# LLC_Demo_Board.net
KiCad netlist of a schematic drawn in EAGLE
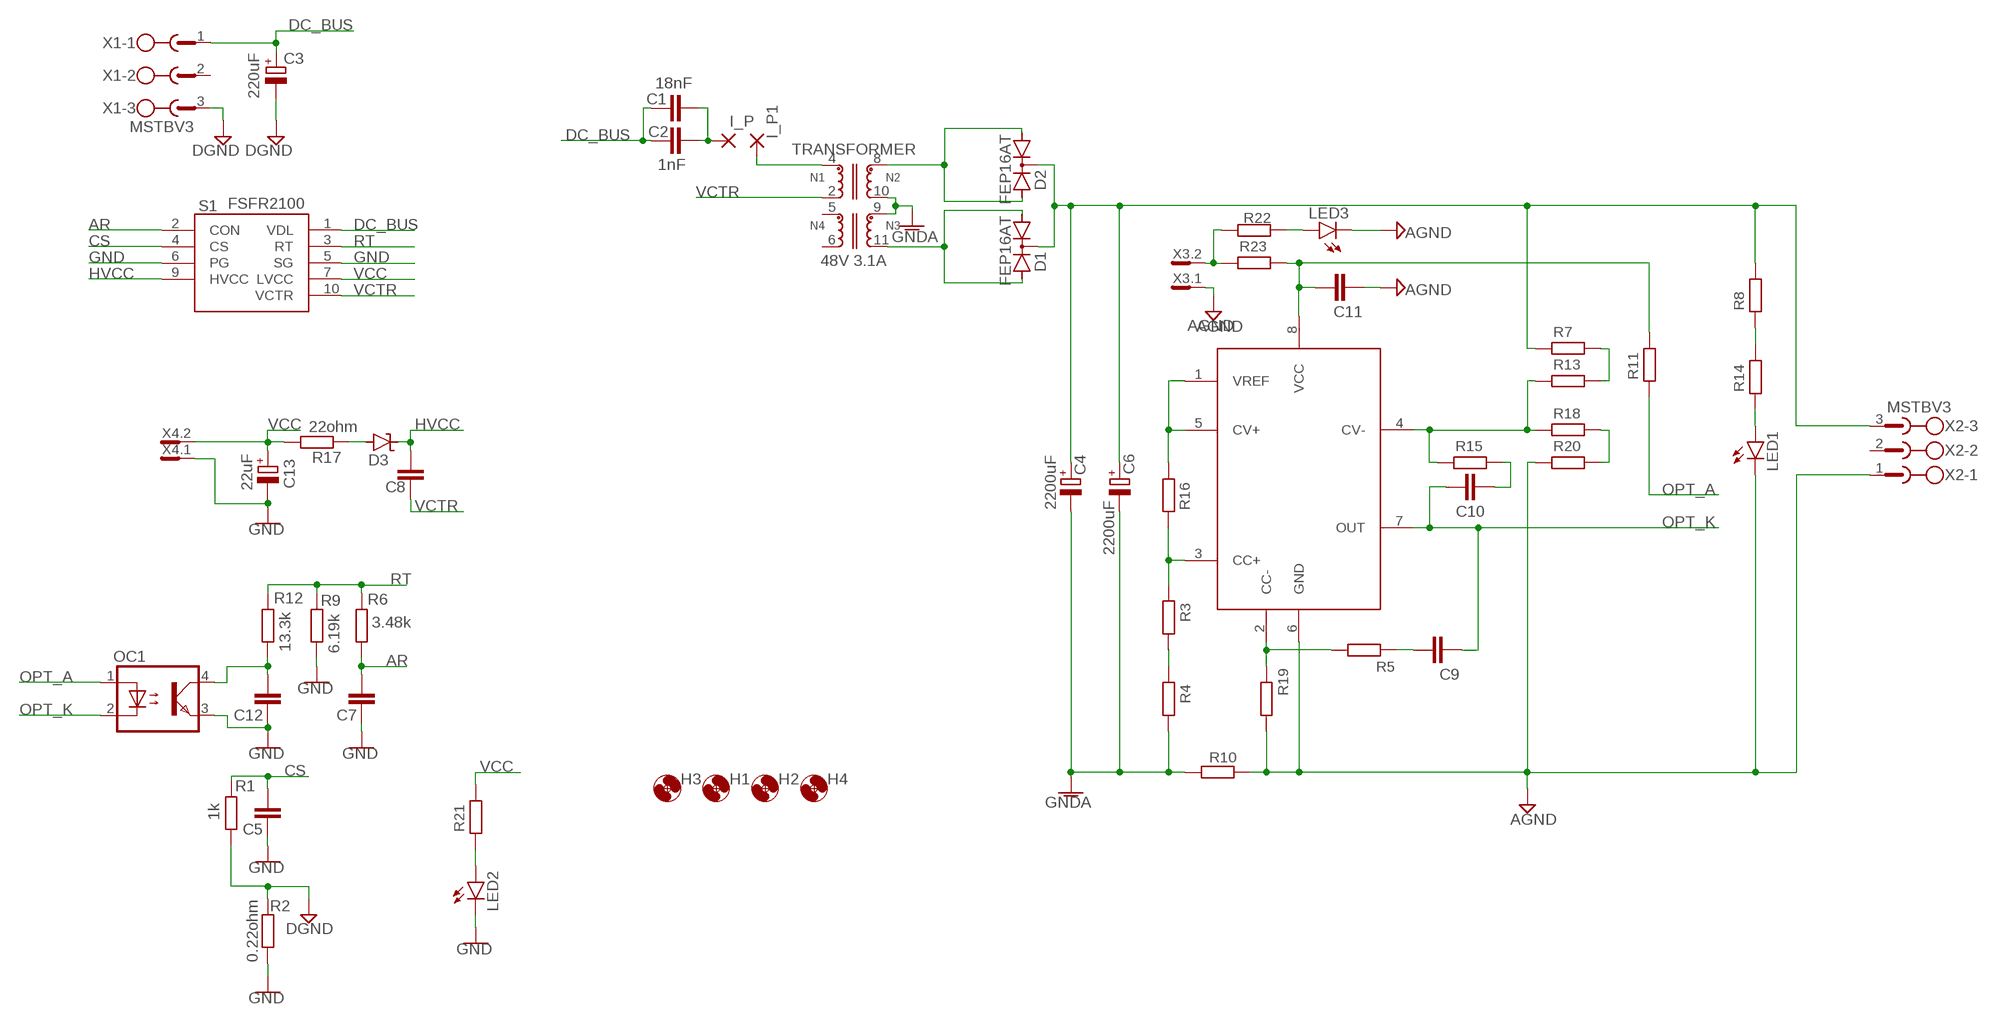
[diagram p0: schematic, sheet 1]

(export (version "E")
  (design (tool "Eeschema 10.0.6"))
  (components
    (comp (ref "C1")
      (value "18nF")
      (footprint "eagle-import:C075-063X106")
      (libsource (lib "eagle-import") (part "rcl_334_C-EU075-063X106"))
    )
    (comp (ref "C2")
      (value "1nF")
      (footprint "eagle-import:C150-072X183")
      (libsource (lib "eagle-import") (part "rcl_334_C-EU150-072X183"))
    )
    (comp (ref "C3")
      (value "220uF")
      (footprint "eagle-import:EB30D")
      (libsource (lib "eagle-import") (part "rcl_334_CPOL-EUE10-30"))
    )
    (comp (ref "C4")
      (value "2200uF")
      (footprint "eagle-import:E7,5-18")
      (libsource (lib "eagle-import") (part "CPOL-EUE7.5-18"))
    )
    (comp (ref "C5")
      (value "100pF")
      (footprint "eagle-import:C0805")
      (libsource (lib "eagle-import") (part "C-EUC0805"))
    )
    (comp (ref "C6")
      (value "2200uF")
      (footprint "eagle-import:E7,5-18")
      (libsource (lib "eagle-import") (part "CPOL-EUE7.5-18"))
    )
    (comp (ref "C7")
      (value "220nF")
      (footprint "eagle-import:C0805")
      (libsource (lib "eagle-import") (part "C-EUC0805"))
    )
    (comp (ref "C8")
      (value "150nF")
      (footprint "eagle-import:C1206")
      (libsource (lib "eagle-import") (part "C-EUC1206"))
    )
    (comp (ref "C9")
      (value "2.2nF")
      (footprint "eagle-import:C1206")
      (libsource (lib "eagle-import") (part "C-EUC1206"))
    )
    (comp (ref "C10")
      (value "2.2nF")
      (footprint "eagle-import:C1206")
      (libsource (lib "eagle-import") (part "C-EUC1206"))
    )
    (comp (ref "C11")
      (value "22uF")
      (footprint "eagle-import:C0805")
      (libsource (lib "eagle-import") (part "C-EUC0805"))
    )
    (comp (ref "C12")
      (value "12nF")
      (footprint "eagle-import:C0805")
      (libsource (lib "eagle-import") (part "C-EUC0805"))
    )
    (comp (ref "C13")
      (value "22uF")
      (footprint "eagle-import:153CLV-0605")
      (libsource (lib "eagle-import") (part "CPOL-EU153CLV-0605"))
    )
    (comp (ref "D1")
      (value "FEP16AT")
      (footprint "eagle-import:TO220ABS")
      (libsource (lib "eagle-import") (part "FEP16AT"))
    )
    (comp (ref "D2")
      (value "FEP16AT")
      (footprint "eagle-import:TO220ABS")
      (libsource (lib "eagle-import") (part "FEP16AT"))
    )
    (comp (ref "D3")
      (value "SUPPRESSOR-SMBJ")
      (footprint "eagle-import:SMBJ")
      (libsource (lib "eagle-import") (part "SUPPRESSOR-SMBJ"))
    )
    (comp (ref "H1")
      (value "MOUNT-HOLE4.1")
      (footprint "eagle-import:4,1")
      (libsource (lib "eagle-import") (part "MOUNT-HOLE4.1"))
    )
    (comp (ref "H2")
      (value "MOUNT-HOLE4.1")
      (footprint "eagle-import:4,1")
      (libsource (lib "eagle-import") (part "MOUNT-HOLE4.1"))
    )
    (comp (ref "H3")
      (value "MOUNT-HOLE4.1")
      (footprint "eagle-import:4,1")
      (libsource (lib "eagle-import") (part "MOUNT-HOLE4.1"))
    )
    (comp (ref "H4")
      (value "MOUNT-HOLE4.1")
      (footprint "eagle-import:4,1")
      (libsource (lib "eagle-import") (part "MOUNT-HOLE4.1"))
    )
    (comp (ref "IC1")
      (value "1039-2224 / TSM1011ID SO-8 Constant Voltage and Constant Current Controller")
      (footprint "eagle-import:SO-8")
      (libsource (lib "eagle-import") (part "TSM1011"))
    )
    (comp (ref "I_P")
      (value "3,81/1,4")
      (footprint "eagle-import:3,81_1,4")
      (libsource (lib "eagle-import") (part "3,81/1,4"))
    )
    (comp (ref "I_P1")
      (value "3,81/1,4")
      (footprint "eagle-import:3,81_1,4")
      (libsource (lib "eagle-import") (part "3,81/1,4"))
    )
    (comp (ref "LED1")
      (value "LED5MM")
      (footprint "eagle-import:LED5MM")
      (libsource (lib "eagle-import") (part "LED5MM"))
    )
    (comp (ref "LED2")
      (value "LED5MM")
      (footprint "eagle-import:LED5MM")
      (libsource (lib "eagle-import") (part "LED5MM"))
    )
    (comp (ref "LED3")
      (value "LED5MM")
      (footprint "eagle-import:LED5MM")
      (libsource (lib "eagle-import") (part "LED5MM"))
    )
    (comp (ref "OC1")
      (value "1039-2189 / Opto coupler CEL-Renesas PS2561DL2-1Y-V-E3-A (8mm creepage ) CTR:50-400")
      (footprint "eagle-import:PS2561DL2-1_OPTO")
      (libsource (lib "eagle-import") (part "PS2561DL2-1_OPTO"))
    )
    (comp (ref "R1")
      (value "1k")
      (footprint "eagle-import:R0805")
      (libsource (lib "eagle-import") (part "R-EU_R0805"))
    )
    (comp (ref "R2")
      (value "0.22ohm")
      (footprint "eagle-import:R2512")
      (libsource (lib "eagle-import") (part "R-EU_R2512"))
    )
    (comp (ref "R3")
      (value "500ohm")
      (footprint "eagle-import:R0805")
      (libsource (lib "eagle-import") (part "R-EU_R0805"))
    )
    (comp (ref "R4")
      (value "500ohm")
      (footprint "eagle-import:R0805")
      (libsource (lib "eagle-import") (part "R-EU_R0805"))
    )
    (comp (ref "R5")
      (value "22k")
      (footprint "eagle-import:R1206")
      (libsource (lib "eagle-import") (part "R-EU_R1206"))
    )
    (comp (ref "R6")
      (value "3.48k")
      (footprint "eagle-import:R0805")
      (libsource (lib "eagle-import") (part "R-EU_R0805"))
    )
    (comp (ref "R7")
      (value "180k")
      (footprint "eagle-import:R1206")
      (libsource (lib "eagle-import") (part "R-EU_R1206"))
    )
    (comp (ref "R8")
      (value "1029-3175 / RES 0805 22K %1")
      (footprint "eagle-import:R1206")
      (libsource (lib "eagle-import") (part "R-EU_R1206"))
    )
    (comp (ref "R9")
      (value "6.19k")
      (footprint "eagle-import:R0805")
      (libsource (lib "eagle-import") (part "R-EU_R0805"))
    )
    (comp (ref "R10")
      (value "50m")
      (footprint "eagle-import:R2512")
      (libsource (lib "eagle-import") (part "R-EU_R2512"))
    )
    (comp (ref "R11")
      (value "100ohm")
      (footprint "eagle-import:R1206")
      (libsource (lib "eagle-import") (part "R-EU_R1206"))
    )
    (comp (ref "R12")
      (value "13.3k")
      (footprint "eagle-import:R0805")
      (libsource (lib "eagle-import") (part "R-EU_R0805"))
    )
    (comp (ref "R13")
      (value "12k")
      (footprint "eagle-import:R1206")
      (libsource (lib "eagle-import") (part "R-EU_R1206"))
    )
    (comp (ref "R14")
      (value "1029-3175 / RES 0805 22K %1")
      (footprint "eagle-import:R1206")
      (libsource (lib "eagle-import") (part "R-EU_R1206"))
    )
    (comp (ref "R15")
      (value "22k")
      (footprint "eagle-import:R1206")
      (libsource (lib "eagle-import") (part "R-EU_R1206"))
    )
    (comp (ref "R16")
      (value "15k")
      (footprint "eagle-import:R0805")
      (libsource (lib "eagle-import") (part "R-EU_R0805"))
    )
    (comp (ref "R17")
      (value "22ohm")
      (footprint "eagle-import:R0805")
      (libsource (lib "eagle-import") (part "R-EU_R0805"))
    )
    (comp (ref "R18")
      (value "4.99k")
      (footprint "eagle-import:R1206")
      (libsource (lib "eagle-import") (part "R-EU_R1206"))
    )
    (comp (ref "R19")
      (value "1k")
      (footprint "eagle-import:R0805")
      (libsource (lib "eagle-import") (part "R-EU_R0805"))
    )
    (comp (ref "R20")
      (value "4.99k")
      (footprint "eagle-import:R1206")
      (libsource (lib "eagle-import") (part "R-EU_R1206"))
    )
    (comp (ref "R21")
      (value "1029-3175 / RES 0805 22K %1")
      (footprint "eagle-import:R1206")
      (libsource (lib "eagle-import") (part "R-EU_R1206"))
    )
    (comp (ref "R22")
      (value "1029-3175 / RES 0805 22K %1")
      (footprint "eagle-import:R1206")
      (libsource (lib "eagle-import") (part "R-EU_R1206"))
    )
    (comp (ref "R23")
      (value "1k")
      (footprint "eagle-import:R1206")
      (libsource (lib "eagle-import") (part "R-EU_R1206"))
    )
    (comp (ref "S1")
      (value "FSFR2100")
      (footprint "eagle-import:FSFR2100")
      (fields (field (name "MOUSER_PART_NUMBER") "512-FSFR2100") (field (name "RS_PART_NUMBER") "6710185P"))
      (libsource (lib "eagle-import") (part "FSFR2100"))
    )
    (comp (ref "TRANSFORMER")
      (value "48V 3.1A")
      (footprint "eagle-import:WE-LLCR_ETD34")
      (libsource (lib "eagle-import") (part "WE-LLCR_ETD34_760895451"))
    )
    (comp (ref "X1")
      (value "MSTBV3")
      (footprint "eagle-import:MSTBV3")
      (fields (field (name "MPN") "MSTBV 2,5/3-GF-5.08"))
      (libsource (lib "eagle-import") (part "MSTBV3"))
    )
    (comp (ref "X2")
      (value "MSTBV3")
      (footprint "eagle-import:MSTBV3")
      (fields (field (name "MPN") "MSTBV 2,5/3-GF-5.08"))
      (libsource (lib "eagle-import") (part "MSTBV3"))
    )
    (comp (ref "X3")
      (value "İKİLİ MOLEX")
      (footprint "eagle-import:MCV2")
      (libsource (lib "eagle-import") (part "MCV2"))
    )
    (comp (ref "X4")
      (value "İKİLİ MOLEX")
      (footprint "eagle-import:MCV2")
      (libsource (lib "eagle-import") (part "MCV2"))
    )
  )
  (nets
    (net (code "1") (name "/AR") (class "Default")
      (node (ref "C7") (pin "1") (pinfunction "1_1") (pintype "passive"))
      (node (ref "R6") (pin "2") (pinfunction "2_2") (pintype "passive"))
      (node (ref "S1") (pin "2") (pinfunction "CON_2") (pintype "bidirectional"))
    )
    (net (code "2") (name "/CS") (class "Default")
      (node (ref "C5") (pin "1") (pinfunction "1_1") (pintype "passive"))
      (node (ref "R1") (pin "2") (pinfunction "2_2") (pintype "passive"))
      (node (ref "S1") (pin "4") (pinfunction "CS_4") (pintype "bidirectional"))
    )
    (net (code "3") (name "/DC_BUS") (class "Default")
      (node (ref "C1") (pin "1") (pinfunction "1_1") (pintype "passive"))
      (node (ref "C2") (pin "1") (pinfunction "1_1") (pintype "passive"))
      (node (ref "C3") (pin "+") (pinfunction "+_+") (pintype "passive"))
      (node (ref "S1") (pin "1") (pinfunction "VDL_1") (pintype "bidirectional"))
      (node (ref "X1") (pin "1") (pinfunction "1_1") (pintype "passive"))
    )
    (net (code "4") (name "/HVCC") (class "Default")
      (node (ref "C8") (pin "1") (pinfunction "1_1") (pintype "passive"))
      (node (ref "D3") (pin "C") (pinfunction "C_C") (pintype "passive"))
      (node (ref "S1") (pin "9") (pinfunction "HVCC_9") (pintype "bidirectional"))
    )
    (net (code "5") (name "/OPT_A") (class "Default")
      (node (ref "OC1") (pin "1") (pinfunction "1_1") (pintype "passive"))
      (node (ref "R11") (pin "2") (pinfunction "2_2") (pintype "passive"))
    )
    (net (code "6") (name "/OPT_K") (class "Default")
      (node (ref "C10") (pin "1") (pinfunction "1_1") (pintype "passive"))
      (node (ref "C9") (pin "1") (pinfunction "1_1") (pintype "passive"))
      (node (ref "IC1") (pin "7") (pinfunction "OUT_7") (pintype "output"))
      (node (ref "OC1") (pin "2") (pinfunction "2_2") (pintype "passive"))
    )
    (net (code "7") (name "/RT") (class "Default")
      (node (ref "R12") (pin "1") (pinfunction "1_1") (pintype "passive"))
      (node (ref "R6") (pin "1") (pinfunction "1_1") (pintype "passive"))
      (node (ref "R9") (pin "1") (pinfunction "1_1") (pintype "passive"))
      (node (ref "S1") (pin "3") (pinfunction "RT_3") (pintype "bidirectional"))
    )
    (net (code "8") (name "/VCC") (class "Default")
      (node (ref "C13") (pin "+") (pinfunction "+_+") (pintype "passive"))
      (node (ref "R17") (pin "2") (pinfunction "2_2") (pintype "passive"))
      (node (ref "R21") (pin "1") (pinfunction "1_1") (pintype "passive"))
      (node (ref "S1") (pin "7") (pinfunction "LVCC_7") (pintype "bidirectional"))
      (node (ref "X4") (pin "2") (pinfunction "SK_2") (pintype "passive"))
    )
    (net (code "9") (name "/VCTR") (class "Default")
      (node (ref "C8") (pin "2") (pinfunction "2_2") (pintype "passive"))
      (node (ref "S1") (pin "10") (pinfunction "VCTR_10") (pintype "bidirectional"))
      (node (ref "TRANSFORMER") (pin "2") (pinfunction "2_2") (pintype "passive"))
    )
    (net (code "10") (name "AGND") (class "Default")
      (node (ref "C11") (pin "1") (pinfunction "1_1") (pintype "passive"))
      (node (ref "IC1") (pin "6") (pinfunction "GND_6") (pintype "power_in"))
      (node (ref "LED1") (pin "K") (pinfunction "C_K") (pintype "passive"))
      (node (ref "LED3") (pin "K") (pinfunction "C_K") (pintype "passive"))
      (node (ref "R10") (pin "2") (pinfunction "2_2") (pintype "passive"))
      (node (ref "R19") (pin "1") (pinfunction "1_1") (pintype "passive"))
      (node (ref "R20") (pin "2") (pinfunction "2_2") (pintype "passive"))
      (node (ref "X2") (pin "1") (pinfunction "1_1") (pintype "passive"))
      (node (ref "X3") (pin "1") (pinfunction "SK_1") (pintype "passive"))
    )
    (net (code "11") (name "DGND") (class "Default")
      (node (ref "C3") (pin "-") (pinfunction "-_-") (pintype "passive"))
      (node (ref "R1") (pin "1") (pinfunction "1_1") (pintype "passive"))
      (node (ref "R2") (pin "2") (pinfunction "2_2") (pintype "passive"))
      (node (ref "X1") (pin "3") (pinfunction "1_3") (pintype "passive"))
    )
    (net (code "12") (name "GND") (class "Default")
      (node (ref "C12") (pin "2") (pinfunction "2_2") (pintype "passive"))
      (node (ref "C13") (pin "-") (pinfunction "-_-") (pintype "passive"))
      (node (ref "C5") (pin "2") (pinfunction "2_2") (pintype "passive"))
      (node (ref "C7") (pin "2") (pinfunction "2_2") (pintype "passive"))
      (node (ref "LED2") (pin "K") (pinfunction "C_K") (pintype "passive"))
      (node (ref "OC1") (pin "3") (pinfunction "3_3") (pintype "passive"))
      (node (ref "R2") (pin "1") (pinfunction "1_1") (pintype "passive"))
      (node (ref "R9") (pin "2") (pinfunction "2_2") (pintype "passive"))
      (node (ref "S1") (pin "5") (pinfunction "SG_5") (pintype "bidirectional"))
      (node (ref "S1") (pin "6") (pinfunction "PG_6") (pintype "bidirectional"))
      (node (ref "X4") (pin "1") (pinfunction "SK_1") (pintype "passive"))
    )
    (net (code "13") (name "GNDA") (class "Default")
      (node (ref "C4") (pin "-") (pinfunction "-_-") (pintype "passive"))
      (node (ref "C6") (pin "-") (pinfunction "-_-") (pintype "passive"))
      (node (ref "R10") (pin "1") (pinfunction "1_1") (pintype "passive"))
      (node (ref "R4") (pin "1") (pinfunction "1_1") (pintype "passive"))
      (node (ref "TRANSFORMER") (pin "10") (pinfunction "7_10") (pintype "passive"))
      (node (ref "TRANSFORMER") (pin "9") (pinfunction "6_9") (pintype "passive"))
    )
    (net (code "14") (name "Net-(C9-Pad2)") (class "Default")
      (node (ref "C9") (pin "2") (pinfunction "2_2") (pintype "passive"))
      (node (ref "R5") (pin "2") (pinfunction "2_2") (pintype "passive"))
    )
    (net (code "15") (name "Net-(C10-Pad2)") (class "Default")
      (node (ref "C10") (pin "2") (pinfunction "2_2") (pintype "passive"))
      (node (ref "R15") (pin "2") (pinfunction "2_2") (pintype "passive"))
    )
    (net (code "16") (name "Net-(C12-Pad1)") (class "Default")
      (node (ref "C12") (pin "1") (pinfunction "1_1") (pintype "passive"))
      (node (ref "OC1") (pin "4") (pinfunction "4_4") (pintype "passive"))
      (node (ref "R12") (pin "2") (pinfunction "2_2") (pintype "passive"))
    )
    (net (code "17") (name "Net-(D2-PadA1)") (class "Default")
      (node (ref "D2") (pin "A1") (pinfunction "A1_A1") (pintype "passive"))
      (node (ref "D2") (pin "A2") (pinfunction "A2_A2") (pintype "passive"))
      (node (ref "TRANSFORMER") (pin "8") (pinfunction "8_8") (pintype "passive"))
    )
    (net (code "18") (name "Net-(D3-PadA)") (class "Default")
      (node (ref "D3") (pin "A") (pinfunction "A_A") (pintype "passive"))
      (node (ref "R17") (pin "1") (pinfunction "1_1") (pintype "passive"))
    )
    (net (code "19") (name "Net-(IC1-CC+)") (class "Default")
      (node (ref "IC1") (pin "3") (pinfunction "CC+_3") (pintype "input"))
      (node (ref "R16") (pin "1") (pinfunction "1_1") (pintype "passive"))
      (node (ref "R3") (pin "2") (pinfunction "2_2") (pintype "passive"))
    )
    (net (code "20") (name "Net-(IC1-CC-)") (class "Default")
      (node (ref "IC1") (pin "2") (pinfunction "CC-_2") (pintype "input"))
      (node (ref "R19") (pin "2") (pinfunction "2_2") (pintype "passive"))
      (node (ref "R5") (pin "1") (pinfunction "1_1") (pintype "passive"))
    )
    (net (code "21") (name "Net-(IC1-CV+)") (class "Default")
      (node (ref "IC1") (pin "1") (pinfunction "VREF_1") (pintype "bidirectional"))
      (node (ref "IC1") (pin "5") (pinfunction "CV+_5") (pintype "input"))
      (node (ref "R16") (pin "2") (pinfunction "2_2") (pintype "passive"))
    )
    (net (code "22") (name "Net-(IC1-CV-)") (class "Default")
      (node (ref "IC1") (pin "4") (pinfunction "CV-_4") (pintype "input"))
      (node (ref "R13") (pin "2") (pinfunction "2_2") (pintype "passive"))
      (node (ref "R15") (pin "1") (pinfunction "1_1") (pintype "passive"))
      (node (ref "R18") (pin "2") (pinfunction "2_2") (pintype "passive"))
    )
    (net (code "23") (name "Net-(IC1-VCC)") (class "Default")
      (node (ref "C11") (pin "2") (pinfunction "2_2") (pintype "passive"))
      (node (ref "IC1") (pin "8") (pinfunction "VCC_8") (pintype "power_in"))
      (node (ref "R11") (pin "1") (pinfunction "1_1") (pintype "passive"))
      (node (ref "R23") (pin "1") (pinfunction "1_1") (pintype "passive"))
    )
    (net (code "24") (name "Net-(I_P-P)") (class "Default")
      (node (ref "C1") (pin "2") (pinfunction "2_2") (pintype "passive"))
      (node (ref "C2") (pin "2") (pinfunction "2_2") (pintype "passive"))
      (node (ref "I_P") (pin "1") (pinfunction "P_1") (pintype "passive"))
    )
    (net (code "25") (name "Net-(I_P1-P)") (class "Default")
      (node (ref "I_P1") (pin "1") (pinfunction "P_1") (pintype "passive"))
      (node (ref "TRANSFORMER") (pin "4") (pinfunction "1_4") (pintype "passive"))
    )
    (net (code "26") (name "Net-(LED1-PadA)") (class "Default")
      (node (ref "LED1") (pin "A") (pinfunction "A_A") (pintype "passive"))
      (node (ref "R14") (pin "2") (pinfunction "2_2") (pintype "passive"))
    )
    (net (code "27") (name "Net-(LED2-PadA)") (class "Default")
      (node (ref "LED2") (pin "A") (pinfunction "A_A") (pintype "passive"))
      (node (ref "R21") (pin "2") (pinfunction "2_2") (pintype "passive"))
    )
    (net (code "28") (name "Net-(LED3-PadA)") (class "Default")
      (node (ref "LED3") (pin "A") (pinfunction "A_A") (pintype "passive"))
      (node (ref "R22") (pin "2") (pinfunction "2_2") (pintype "passive"))
    )
    (net (code "29") (name "Net-(R3-Pad1)") (class "Default")
      (node (ref "R3") (pin "1") (pinfunction "1_1") (pintype "passive"))
      (node (ref "R4") (pin "2") (pinfunction "2_2") (pintype "passive"))
    )
    (net (code "30") (name "Net-(R13-Pad1)") (class "Default")
      (node (ref "R13") (pin "1") (pinfunction "1_1") (pintype "passive"))
      (node (ref "R7") (pin "1") (pinfunction "1_1") (pintype "passive"))
    )
    (net (code "31") (name "Net-(R14-Pad1)") (class "Default")
      (node (ref "R14") (pin "1") (pinfunction "1_1") (pintype "passive"))
      (node (ref "R8") (pin "2") (pinfunction "2_2") (pintype "passive"))
    )
    (net (code "32") (name "Net-(R18-Pad1)") (class "Default")
      (node (ref "R18") (pin "1") (pinfunction "1_1") (pintype "passive"))
      (node (ref "R20") (pin "1") (pinfunction "1_1") (pintype "passive"))
    )
    (net (code "33") (name "Net-(TRANSFORMER-5)") (class "Default")
      (node (ref "D1") (pin "A1") (pinfunction "A1_A1") (pintype "passive"))
      (node (ref "D1") (pin "A2") (pinfunction "A2_A2") (pintype "passive"))
      (node (ref "TRANSFORMER") (pin "11") (pinfunction "5_11") (pintype "passive"))
    )
    (net (code "34") (name "Net-(X2C-1)") (class "Default")
      (node (ref "C4") (pin "+") (pinfunction "+_+") (pintype "passive"))
      (node (ref "C6") (pin "+") (pinfunction "+_+") (pintype "passive"))
      (node (ref "D1") (pin "C") (pinfunction "C_C") (pintype "passive"))
      (node (ref "D2") (pin "C") (pinfunction "C_C") (pintype "passive"))
      (node (ref "R7") (pin "2") (pinfunction "2_2") (pintype "passive"))
      (node (ref "R8") (pin "1") (pinfunction "1_1") (pintype "passive"))
      (node (ref "X2") (pin "3") (pinfunction "1_3") (pintype "passive"))
    )
    (net (code "35") (name "Net-(X3B-SK)") (class "Default")
      (node (ref "R22") (pin "1") (pinfunction "1_1") (pintype "passive"))
      (node (ref "R23") (pin "2") (pinfunction "2_2") (pintype "passive"))
      (node (ref "X3") (pin "2") (pinfunction "SK_2") (pintype "passive"))
    )
    (net (code "36") (name "unconnected-(TRANSFORMER-3-Pad5)") (class "Default")
      (node (ref "TRANSFORMER") (pin "5") (pinfunction "3_5") (pintype "passive"))
    )
    (net (code "37") (name "unconnected-(TRANSFORMER-4-Pad6)") (class "Default")
      (node (ref "TRANSFORMER") (pin "6") (pinfunction "4_6") (pintype "passive"))
    )
    (net (code "38") (name "unconnected-(X1B-1-Pad2)") (class "Default")
      (node (ref "X1") (pin "2") (pinfunction "1_2") (pintype "passive"))
    )
    (net (code "39") (name "unconnected-(X2B-1-Pad2)") (class "Default")
      (node (ref "X2") (pin "2") (pinfunction "1_2") (pintype "passive"))
    )
  )
)
